# dualpower.net
KiCad netlist of a schematic drawn in EAGLE
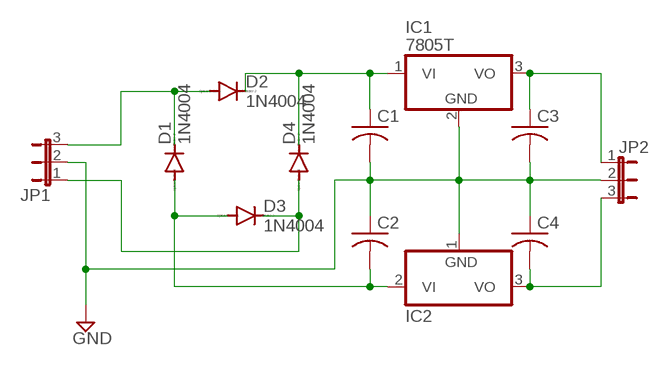
[diagram p0: schematic, sheet 1]

(export (version "E")
  (design (tool "Eeschema 10.0.6"))
  (components
    (comp (ref "C1")
      (value "C-US025-024X044")
      (footprint "eagle-import:C025-024X044")
      (libsource (lib "eagle-import") (part "C-US025-024X044"))
    )
    (comp (ref "C2")
      (value "C-US025-024X044")
      (footprint "eagle-import:C025-024X044")
      (libsource (lib "eagle-import") (part "C-US025-024X044"))
    )
    (comp (ref "C3")
      (value "C-US025-024X044")
      (footprint "eagle-import:C025-024X044")
      (libsource (lib "eagle-import") (part "C-US025-024X044"))
    )
    (comp (ref "C4")
      (value "C-US025-024X044")
      (footprint "eagle-import:C025-024X044")
      (libsource (lib "eagle-import") (part "C-US025-024X044"))
    )
    (comp (ref "D1")
      (value "1N4004")
      (footprint "eagle-import:DO41-10")
      (libsource (lib "eagle-import") (part "1N4004"))
    )
    (comp (ref "D2")
      (value "1N4004")
      (footprint "eagle-import:DO41-10")
      (libsource (lib "eagle-import") (part "1N4004"))
    )
    (comp (ref "D3")
      (value "1N4004")
      (footprint "eagle-import:DO41-10")
      (libsource (lib "eagle-import") (part "1N4004"))
    )
    (comp (ref "D4")
      (value "1N4004")
      (footprint "eagle-import:DO41-10")
      (libsource (lib "eagle-import") (part "1N4004"))
    )
    (comp (ref "IC1")
      (value "7805T")
      (footprint "eagle-import:TO220H")
      (libsource (lib "eagle-import") (part "78T05"))
    )
    (comp (ref "IC2")
      (value "79L05Z")
      (footprint "eagle-import:TO92")
      (libsource (lib "eagle-import") (part "79ZL05"))
    )
    (comp (ref "JP1")
      (value "JP2W")
      (footprint "eagle-import:JP2W")
      (libsource (lib "eagle-import") (part "JP2W"))
    )
    (comp (ref "JP2")
      (value "JP2W")
      (footprint "eagle-import:JP2W")
      (libsource (lib "eagle-import") (part "JP2W"))
    )
  )
  (nets
    (net (code "1") (name "GND") (class "Default")
      (node (ref "C1") (pin "2") (pinfunction "2_2") (pintype "passive"))
      (node (ref "C2") (pin "1") (pinfunction "1_1") (pintype "passive"))
      (node (ref "C3") (pin "2") (pinfunction "2_2") (pintype "passive"))
      (node (ref "C4") (pin "1") (pinfunction "1_1") (pintype "passive"))
      (node (ref "IC1") (pin "2") (pinfunction "GND_2") (pintype "passive"))
      (node (ref "IC2") (pin "1") (pinfunction "GND_1") (pintype "passive"))
      (node (ref "JP1") (pin "2") (pinfunction "2_2") (pintype "passive"))
      (node (ref "JP2") (pin "2") (pinfunction "2_2") (pintype "passive"))
    )
    (net (code "2") (name "Net-(D1-PadC)") (class "Default")
      (node (ref "D1") (pin "C") (pinfunction "C_C") (pintype "passive"))
      (node (ref "D2") (pin "A") (pinfunction "A_A") (pintype "passive"))
      (node (ref "JP1") (pin "3") (pinfunction "3_3") (pintype "passive"))
    )
    (net (code "3") (name "Net-(D3-PadC)") (class "Default")
      (node (ref "D3") (pin "C") (pinfunction "C_C") (pintype "passive"))
      (node (ref "D4") (pin "A") (pinfunction "A_A") (pintype "passive"))
      (node (ref "JP1") (pin "1") (pinfunction "1_1") (pintype "passive"))
    )
    (net (code "4") (name "Net-(IC1-VI)") (class "Default")
      (node (ref "C1") (pin "1") (pinfunction "1_1") (pintype "passive"))
      (node (ref "D2") (pin "C") (pinfunction "C_C") (pintype "passive"))
      (node (ref "D4") (pin "C") (pinfunction "C_C") (pintype "passive"))
      (node (ref "IC1") (pin "1") (pinfunction "VI_1") (pintype "input"))
    )
    (net (code "5") (name "Net-(IC1-VO)") (class "Default")
      (node (ref "C3") (pin "1") (pinfunction "1_1") (pintype "passive"))
      (node (ref "IC1") (pin "3") (pinfunction "VO_3") (pintype "passive"))
      (node (ref "JP2") (pin "1") (pinfunction "1_1") (pintype "passive"))
    )
    (net (code "6") (name "Net-(IC2-VI)") (class "Default")
      (node (ref "C2") (pin "2") (pinfunction "2_2") (pintype "passive"))
      (node (ref "D1") (pin "A") (pinfunction "A_A") (pintype "passive"))
      (node (ref "D3") (pin "A") (pinfunction "A_A") (pintype "passive"))
      (node (ref "IC2") (pin "2") (pinfunction "VI_2") (pintype "input"))
    )
    (net (code "7") (name "Net-(IC2-VO)") (class "Default")
      (node (ref "C4") (pin "2") (pinfunction "2_2") (pintype "passive"))
      (node (ref "IC2") (pin "3") (pinfunction "VO_3") (pintype "passive"))
      (node (ref "JP2") (pin "3") (pinfunction "3_3") (pintype "passive"))
    )
  )
)
